# CLK.net
KiCad netlist of a schematic drawn in EAGLE
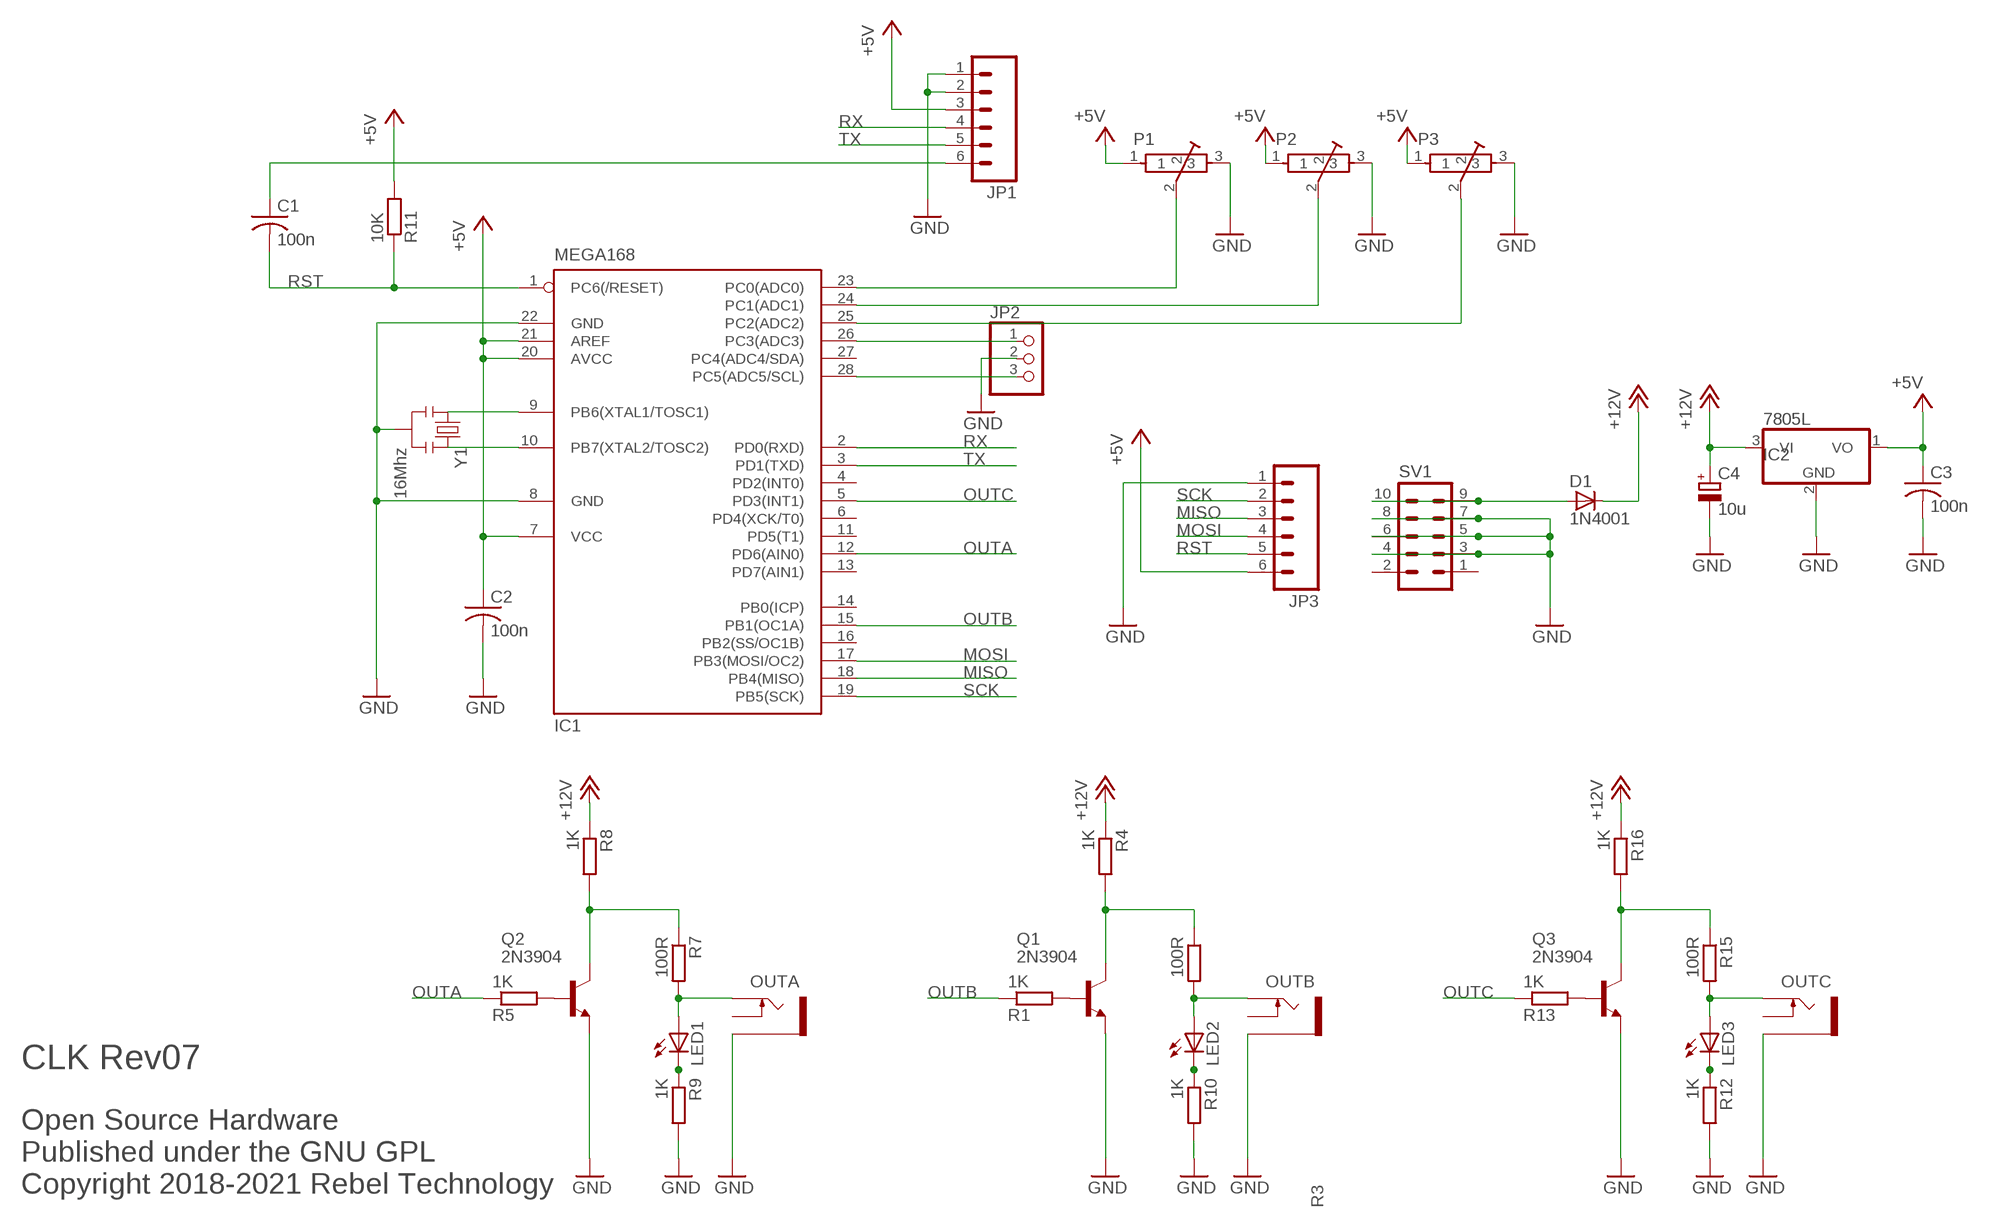
[diagram p0: schematic, sheet 1]

(export (version "E")
  (design (tool "Eeschema 10.0.6"))
  (components
    (comp (ref "C1")
      (value "100n")
      (footprint "eagle-import:C050-024X044")
      (libsource (lib "eagle-import") (part "C-US050-024X044"))
    )
    (comp (ref "C2")
      (value "100n")
      (footprint "eagle-import:C050-024X044")
      (libsource (lib "eagle-import") (part "C-US050-024X044"))
    )
    (comp (ref "C3")
      (value "100n")
      (footprint "eagle-import:C050-024X044")
      (libsource (lib "eagle-import") (part "C-US050-024X044"))
    )
    (comp (ref "C4")
      (value "10u")
      (footprint "eagle-import:E5-6")
      (libsource (lib "eagle-import") (part "CPOL-EUE5-6"))
    )
    (comp (ref "D1")
      (value "1N4001")
      (footprint "eagle-import:DIODE-1N4001")
      (libsource (lib "eagle-import") (part "DIODE1N4001"))
    )
    (comp (ref "IC1")
      (value "MEGA168")
      (footprint "eagle-import:DIL28-3")
      (libsource (lib "eagle-import") (part "MEGA8-P"))
    )
    (comp (ref "IC2")
      (value "7805L")
      (footprint "eagle-import:TO92")
      (libsource (lib "eagle-import") (part "78L05"))
    )
    (comp (ref "JP1")
      (value "M06SIP")
      (footprint "eagle-import:1X06")
      (libsource (lib "eagle-import") (part "M06SIP"))
    )
    (comp (ref "JP2")
      (value "PINHD-1X3")
      (footprint "eagle-import:1X03")
      (libsource (lib "eagle-import") (part "PINHD-1X3"))
    )
    (comp (ref "JP3")
      (value "M06SIP")
      (footprint "eagle-import:1X06")
      (libsource (lib "eagle-import") (part "M06SIP"))
    )
    (comp (ref "LED1")
      (value "LED3MM")
      (footprint "eagle-import:LED3MM")
      (libsource (lib "eagle-import") (part "LED3MM"))
    )
    (comp (ref "LED2")
      (value "LED3MM")
      (footprint "eagle-import:LED3MM")
      (libsource (lib "eagle-import") (part "LED3MM"))
    )
    (comp (ref "LED3")
      (value "LED3MM")
      (footprint "eagle-import:LED3MM")
      (libsource (lib "eagle-import") (part "LED3MM"))
    )
    (comp (ref "OUTA")
      (value "PJ302M")
      (footprint "eagle-import:PJ302M")
      (libsource (lib "eagle-import") (part "PJ302M"))
    )
    (comp (ref "OUTB")
      (value "PJ302M")
      (footprint "eagle-import:PJ302M")
      (libsource (lib "eagle-import") (part "PJ302M"))
    )
    (comp (ref "OUTC")
      (value "PJ302M")
      (footprint "eagle-import:PJ302M")
      (libsource (lib "eagle-import") (part "PJ302M"))
    )
    (comp (ref "P1")
      (value "POT-BOURNS-PTD901")
      (footprint "eagle-import:POT-BOURNS-PTD901")
      (libsource (lib "eagle-import") (part "POT-BOURNS-PTD901"))
    )
    (comp (ref "P2")
      (value "POT-BOURNS-PTD901")
      (footprint "eagle-import:POT-BOURNS-PTD901")
      (libsource (lib "eagle-import") (part "POT-BOURNS-PTD901"))
    )
    (comp (ref "P3")
      (value "POT-BOURNS-PTD901")
      (footprint "eagle-import:POT-BOURNS-PTD901")
      (libsource (lib "eagle-import") (part "POT-BOURNS-PTD901"))
    )
    (comp (ref "Q1")
      (value "2N3904")
      (footprint "eagle-import:TO92")
      (libsource (lib "eagle-import") (part "2N3904"))
    )
    (comp (ref "Q2")
      (value "2N3904")
      (footprint "eagle-import:TO92")
      (libsource (lib "eagle-import") (part "2N3904"))
    )
    (comp (ref "Q3")
      (value "2N3904")
      (footprint "eagle-import:TO92")
      (libsource (lib "eagle-import") (part "2N3904"))
    )
    (comp (ref "R1")
      (value "1K")
      (footprint "eagle-import:0204_7")
      (libsource (lib "eagle-import") (part "R-EU_0204/7"))
    )
    (comp (ref "R3")
      (value "100R")
      (footprint "eagle-import:0204_7")
      (libsource (lib "eagle-import") (part "R-EU_0204/7"))
    )
    (comp (ref "R4")
      (value "1K")
      (footprint "eagle-import:0204_7")
      (libsource (lib "eagle-import") (part "R-EU_0204/7"))
    )
    (comp (ref "R5")
      (value "1K")
      (footprint "eagle-import:0204_7")
      (libsource (lib "eagle-import") (part "R-EU_0204/7"))
    )
    (comp (ref "R7")
      (value "100R")
      (footprint "eagle-import:0204_7")
      (libsource (lib "eagle-import") (part "R-EU_0204/7"))
    )
    (comp (ref "R8")
      (value "1K")
      (footprint "eagle-import:0204_7")
      (libsource (lib "eagle-import") (part "R-EU_0204/7"))
    )
    (comp (ref "R9")
      (value "1K")
      (footprint "eagle-import:0204_7")
      (libsource (lib "eagle-import") (part "R-EU_0204/7"))
    )
    (comp (ref "R10")
      (value "1K")
      (footprint "eagle-import:0204_7")
      (libsource (lib "eagle-import") (part "R-EU_0204/7"))
    )
    (comp (ref "R11")
      (value "10K")
      (footprint "eagle-import:0204_7")
      (libsource (lib "eagle-import") (part "R-EU_0204/7"))
    )
    (comp (ref "R12")
      (value "1K")
      (footprint "eagle-import:0204_7")
      (libsource (lib "eagle-import") (part "R-EU_0204/7"))
    )
    (comp (ref "R13")
      (value "1K")
      (footprint "eagle-import:0204_7")
      (libsource (lib "eagle-import") (part "R-EU_0204/7"))
    )
    (comp (ref "R15")
      (value "100R")
      (footprint "eagle-import:0204_7")
      (libsource (lib "eagle-import") (part "R-EU_0204/7"))
    )
    (comp (ref "R16")
      (value "1K")
      (footprint "eagle-import:0204_7")
      (libsource (lib "eagle-import") (part "R-EU_0204/7"))
    )
    (comp (ref "SV1")
      (value "MA05-2")
      (footprint "eagle-import:MA05-2")
      (libsource (lib "eagle-import") (part "MA05-2"))
    )
    (comp (ref "Y1")
      (value "16Mhz")
      (footprint "eagle-import:RESONATOR-PTH")
      (libsource (lib "eagle-import") (part "RESONATORPTH"))
    )
  )
  (nets
    (net (code "1") (name "+5V") (class "Default")
      (node (ref "C2") (pin "1") (pinfunction "1_1") (pintype "passive"))
      (node (ref "C3") (pin "1") (pinfunction "1_1") (pintype "passive"))
      (node (ref "IC1") (pin "20") (pinfunction "AVCC_20") (pintype "power_in"))
      (node (ref "IC1") (pin "21") (pinfunction "AREF_21") (pintype "passive"))
      (node (ref "IC1") (pin "7") (pinfunction "VCC_7") (pintype "power_in"))
      (node (ref "IC2") (pin "1") (pinfunction "VO_1") (pintype "passive"))
      (node (ref "JP1") (pin "3") (pinfunction "3_3") (pintype "passive"))
      (node (ref "JP3") (pin "6") (pinfunction "6_6") (pintype "passive"))
      (node (ref "P1") (pin "1") (pinfunction "1_1") (pintype "bidirectional"))
      (node (ref "P2") (pin "1") (pinfunction "1_1") (pintype "bidirectional"))
      (node (ref "P3") (pin "1") (pinfunction "1_1") (pintype "bidirectional"))
      (node (ref "R11") (pin "2") (pinfunction "2_2") (pintype "passive"))
    )
    (net (code "2") (name "+12V") (class "Default")
      (node (ref "C4") (pin "+") (pinfunction "+_+") (pintype "passive"))
      (node (ref "D1") (pin "C") (pinfunction "C_C") (pintype "passive"))
      (node (ref "IC2") (pin "3") (pinfunction "VI_3") (pintype "input"))
      (node (ref "R16") (pin "1") (pinfunction "1_1") (pintype "passive"))
      (node (ref "R4") (pin "1") (pinfunction "1_1") (pintype "passive"))
      (node (ref "R8") (pin "1") (pinfunction "1_1") (pintype "passive"))
    )
    (net (code "3") (name "/MISO") (class "Default")
      (node (ref "IC1") (pin "18") (pinfunction "PB4(MISO)_18") (pintype "bidirectional"))
      (node (ref "JP3") (pin "3") (pinfunction "3_3") (pintype "passive"))
    )
    (net (code "4") (name "/MOSI") (class "Default")
      (node (ref "IC1") (pin "17") (pinfunction "PB3(MOSI/OC2)_17") (pintype "bidirectional"))
      (node (ref "JP3") (pin "4") (pinfunction "4_4") (pintype "passive"))
    )
    (net (code "5") (name "/OUTA") (class "Default")
      (node (ref "IC1") (pin "12") (pinfunction "PD6(AIN0)_12") (pintype "bidirectional"))
      (node (ref "R5") (pin "1") (pinfunction "1_1") (pintype "passive"))
    )
    (net (code "6") (name "/OUTB") (class "Default")
      (node (ref "IC1") (pin "15") (pinfunction "PB1(OC1A)_15") (pintype "bidirectional"))
      (node (ref "R1") (pin "1") (pinfunction "1_1") (pintype "passive"))
    )
    (net (code "7") (name "/OUTC") (class "Default")
      (node (ref "IC1") (pin "5") (pinfunction "PD3(INT1)_5") (pintype "bidirectional"))
      (node (ref "R13") (pin "1") (pinfunction "1_1") (pintype "passive"))
    )
    (net (code "8") (name "/RST") (class "Default")
      (node (ref "C1") (pin "2") (pinfunction "2_2") (pintype "passive"))
      (node (ref "IC1") (pin "1") (pinfunction "PC6(/RESET)_1") (pintype "bidirectional"))
      (node (ref "JP3") (pin "5") (pinfunction "5_5") (pintype "passive"))
      (node (ref "R11") (pin "1") (pinfunction "1_1") (pintype "passive"))
    )
    (net (code "9") (name "/RX") (class "Default")
      (node (ref "IC1") (pin "2") (pinfunction "PD0(RXD)_2") (pintype "bidirectional"))
      (node (ref "JP1") (pin "4") (pinfunction "4_4") (pintype "passive"))
    )
    (net (code "10") (name "/SCK") (class "Default")
      (node (ref "IC1") (pin "19") (pinfunction "PB5(SCK)_19") (pintype "bidirectional"))
      (node (ref "JP3") (pin "2") (pinfunction "2_2") (pintype "passive"))
    )
    (net (code "11") (name "/TX") (class "Default")
      (node (ref "IC1") (pin "3") (pinfunction "PD1(TXD)_3") (pintype "bidirectional"))
      (node (ref "JP1") (pin "5") (pinfunction "5_5") (pintype "passive"))
    )
    (net (code "12") (name "GND") (class "Default")
      (node (ref "C2") (pin "2") (pinfunction "2_2") (pintype "passive"))
      (node (ref "C3") (pin "2") (pinfunction "2_2") (pintype "passive"))
      (node (ref "C4") (pin "-") (pinfunction "-_-") (pintype "passive"))
      (node (ref "IC1") (pin "22") (pinfunction "GND_22") (pintype "power_in"))
      (node (ref "IC1") (pin "8") (pinfunction "GND_8") (pintype "power_in"))
      (node (ref "IC2") (pin "2") (pinfunction "GND_2") (pintype "passive"))
      (node (ref "JP1") (pin "1") (pinfunction "1_1") (pintype "passive"))
      (node (ref "JP1") (pin "2") (pinfunction "2_2") (pintype "passive"))
      (node (ref "JP2") (pin "2") (pinfunction "2_2") (pintype "passive"))
      (node (ref "JP3") (pin "1") (pinfunction "1_1") (pintype "passive"))
      (node (ref "OUTA") (pin "GND") (pinfunction "SLEEVE_GND") (pintype "passive"))
      (node (ref "OUTB") (pin "GND") (pinfunction "SLEEVE_GND") (pintype "passive"))
      (node (ref "OUTC") (pin "GND") (pinfunction "SLEEVE_GND") (pintype "passive"))
      (node (ref "P1") (pin "3") (pinfunction "3_3") (pintype "bidirectional"))
      (node (ref "P2") (pin "3") (pinfunction "3_3") (pintype "bidirectional"))
      (node (ref "P3") (pin "3") (pinfunction "3_3") (pintype "bidirectional"))
      (node (ref "Q1") (pin "3") (pinfunction "E_3") (pintype "passive"))
      (node (ref "Q2") (pin "3") (pinfunction "E_3") (pintype "passive"))
      (node (ref "Q3") (pin "3") (pinfunction "E_3") (pintype "passive"))
      (node (ref "R10") (pin "2") (pinfunction "2_2") (pintype "passive"))
      (node (ref "R12") (pin "2") (pinfunction "2_2") (pintype "passive"))
      (node (ref "R9") (pin "2") (pinfunction "2_2") (pintype "passive"))
      (node (ref "SV1") (pin "3") (pinfunction "3_3") (pintype "passive"))
      (node (ref "SV1") (pin "4") (pinfunction "4_4") (pintype "passive"))
      (node (ref "SV1") (pin "5") (pinfunction "5_5") (pintype "passive"))
      (node (ref "SV1") (pin "6") (pinfunction "6_6") (pintype "passive"))
      (node (ref "SV1") (pin "7") (pinfunction "7_7") (pintype "passive"))
      (node (ref "SV1") (pin "8") (pinfunction "8_8") (pintype "passive"))
      (node (ref "Y1") (pin "2") (pinfunction "2_2") (pintype "passive"))
    )
    (net (code "13") (name "Net-(C1-Pad1)") (class "Default")
      (node (ref "C1") (pin "1") (pinfunction "1_1") (pintype "passive"))
      (node (ref "JP1") (pin "6") (pinfunction "6_6") (pintype "passive"))
    )
    (net (code "14") (name "Net-(D1-PadA)") (class "Default")
      (node (ref "D1") (pin "A") (pinfunction "A_A") (pintype "passive"))
      (node (ref "SV1") (pin "10") (pinfunction "10_10") (pintype "passive"))
      (node (ref "SV1") (pin "9") (pinfunction "9_9") (pintype "passive"))
    )
    (net (code "15") (name "Net-(IC1-PB6(XTAL1{slash}TOSC1))") (class "Default")
      (node (ref "IC1") (pin "9") (pinfunction "PB6(XTAL1/TOSC1)_9") (pintype "bidirectional"))
      (node (ref "Y1") (pin "1") (pinfunction "1_1") (pintype "passive"))
    )
    (net (code "16") (name "Net-(IC1-PB7(XTAL2{slash}TOSC2))") (class "Default")
      (node (ref "IC1") (pin "10") (pinfunction "PB7(XTAL2/TOSC2)_10") (pintype "bidirectional"))
      (node (ref "Y1") (pin "3") (pinfunction "3_3") (pintype "passive"))
    )
    (net (code "17") (name "Net-(IC1-PC0(ADC0))") (class "Default")
      (node (ref "IC1") (pin "23") (pinfunction "PC0(ADC0)_23") (pintype "bidirectional"))
      (node (ref "P1") (pin "2") (pinfunction "2_2") (pintype "bidirectional"))
    )
    (net (code "18") (name "Net-(IC1-PC1(ADC1))") (class "Default")
      (node (ref "IC1") (pin "24") (pinfunction "PC1(ADC1)_24") (pintype "bidirectional"))
      (node (ref "P2") (pin "2") (pinfunction "2_2") (pintype "bidirectional"))
    )
    (net (code "19") (name "Net-(IC1-PC2(ADC2))") (class "Default")
      (node (ref "IC1") (pin "25") (pinfunction "PC2(ADC2)_25") (pintype "bidirectional"))
      (node (ref "P3") (pin "2") (pinfunction "2_2") (pintype "bidirectional"))
    )
    (net (code "20") (name "Net-(IC1-PC3(ADC3))") (class "Default")
      (node (ref "IC1") (pin "26") (pinfunction "PC3(ADC3)_26") (pintype "bidirectional"))
      (node (ref "JP2") (pin "1") (pinfunction "1_1") (pintype "passive"))
    )
    (net (code "21") (name "Net-(IC1-PC5(ADC5{slash}SCL))") (class "Default")
      (node (ref "IC1") (pin "28") (pinfunction "PC5(ADC5/SCL)_28") (pintype "bidirectional"))
      (node (ref "JP2") (pin "3") (pinfunction "3_3") (pintype "passive"))
    )
    (net (code "22") (name "Net-(LED1-C)") (class "Default")
      (node (ref "LED1") (pin "K") (pinfunction "C_K") (pintype "passive"))
      (node (ref "R9") (pin "1") (pinfunction "1_1") (pintype "passive"))
    )
    (net (code "23") (name "Net-(LED1-PadA)") (class "Default")
      (node (ref "LED1") (pin "A") (pinfunction "A_A") (pintype "passive"))
      (node (ref "OUTA") (pin "TIP") (pinfunction "TIP_TIP") (pintype "passive"))
      (node (ref "R7") (pin "2") (pinfunction "2_2") (pintype "passive"))
    )
    (net (code "24") (name "Net-(LED2-C)") (class "Default")
      (node (ref "LED2") (pin "K") (pinfunction "C_K") (pintype "passive"))
      (node (ref "R10") (pin "1") (pinfunction "1_1") (pintype "passive"))
    )
    (net (code "25") (name "Net-(LED2-PadA)") (class "Default")
      (node (ref "LED2") (pin "A") (pinfunction "A_A") (pintype "passive"))
      (node (ref "OUTB") (pin "TIP") (pinfunction "TIP_TIP") (pintype "passive"))
      (node (ref "R3") (pin "2") (pinfunction "2_2") (pintype "passive"))
    )
    (net (code "26") (name "Net-(LED3-C)") (class "Default")
      (node (ref "LED3") (pin "K") (pinfunction "C_K") (pintype "passive"))
      (node (ref "R12") (pin "1") (pinfunction "1_1") (pintype "passive"))
    )
    (net (code "27") (name "Net-(LED3-PadA)") (class "Default")
      (node (ref "LED3") (pin "A") (pinfunction "A_A") (pintype "passive"))
      (node (ref "OUTC") (pin "TIP") (pinfunction "TIP_TIP") (pintype "passive"))
      (node (ref "R15") (pin "2") (pinfunction "2_2") (pintype "passive"))
    )
    (net (code "28") (name "Net-(Q1-B)") (class "Default")
      (node (ref "Q1") (pin "2") (pinfunction "B_2") (pintype "passive"))
      (node (ref "R1") (pin "2") (pinfunction "2_2") (pintype "passive"))
    )
    (net (code "29") (name "Net-(Q1-C)") (class "Default")
      (node (ref "Q1") (pin "1") (pinfunction "C_1") (pintype "passive"))
      (node (ref "R3") (pin "1") (pinfunction "1_1") (pintype "passive"))
      (node (ref "R4") (pin "2") (pinfunction "2_2") (pintype "passive"))
    )
    (net (code "30") (name "Net-(Q2-B)") (class "Default")
      (node (ref "Q2") (pin "2") (pinfunction "B_2") (pintype "passive"))
      (node (ref "R5") (pin "2") (pinfunction "2_2") (pintype "passive"))
    )
    (net (code "31") (name "Net-(Q2-C)") (class "Default")
      (node (ref "Q2") (pin "1") (pinfunction "C_1") (pintype "passive"))
      (node (ref "R7") (pin "1") (pinfunction "1_1") (pintype "passive"))
      (node (ref "R8") (pin "2") (pinfunction "2_2") (pintype "passive"))
    )
    (net (code "32") (name "Net-(Q3-B)") (class "Default")
      (node (ref "Q3") (pin "2") (pinfunction "B_2") (pintype "passive"))
      (node (ref "R13") (pin "2") (pinfunction "2_2") (pintype "passive"))
    )
    (net (code "33") (name "Net-(Q3-C)") (class "Default")
      (node (ref "Q3") (pin "1") (pinfunction "C_1") (pintype "passive"))
      (node (ref "R15") (pin "1") (pinfunction "1_1") (pintype "passive"))
      (node (ref "R16") (pin "2") (pinfunction "2_2") (pintype "passive"))
    )
    (net (code "34") (name "unconnected-(IC1-PB0(ICP)-Pad14)") (class "Default")
      (node (ref "IC1") (pin "14") (pinfunction "PB0(ICP)_14") (pintype "bidirectional"))
    )
    (net (code "35") (name "unconnected-(IC1-PB2(SS{slash}OC1B)-Pad16)") (class "Default")
      (node (ref "IC1") (pin "16") (pinfunction "PB2(SS/OC1B)_16") (pintype "bidirectional"))
    )
    (net (code "36") (name "unconnected-(IC1-PC4(ADC4{slash}SDA)-Pad27)") (class "Default")
      (node (ref "IC1") (pin "27") (pinfunction "PC4(ADC4/SDA)_27") (pintype "bidirectional"))
    )
    (net (code "37") (name "unconnected-(IC1-PD2(INT0)-Pad4)") (class "Default")
      (node (ref "IC1") (pin "4") (pinfunction "PD2(INT0)_4") (pintype "bidirectional"))
    )
    (net (code "38") (name "unconnected-(IC1-PD4(XCK{slash}T0)-Pad6)") (class "Default")
      (node (ref "IC1") (pin "6") (pinfunction "PD4(XCK/T0)_6") (pintype "bidirectional"))
    )
    (net (code "39") (name "unconnected-(IC1-PD5(T1)-Pad11)") (class "Default")
      (node (ref "IC1") (pin "11") (pinfunction "PD5(T1)_11") (pintype "bidirectional"))
    )
    (net (code "40") (name "unconnected-(IC1-PD7(AIN1)-Pad13)") (class "Default")
      (node (ref "IC1") (pin "13") (pinfunction "PD7(AIN1)_13") (pintype "bidirectional"))
    )
    (net (code "41") (name "unconnected-(OUTA-SWITCH-PadSW)") (class "Default")
      (node (ref "OUTA") (pin "SW") (pinfunction "SWITCH_SW") (pintype "passive"))
    )
    (net (code "42") (name "unconnected-(OUTB-SWITCH-PadSW)") (class "Default")
      (node (ref "OUTB") (pin "SW") (pinfunction "SWITCH_SW") (pintype "passive"))
    )
    (net (code "43") (name "unconnected-(OUTC-SWITCH-PadSW)") (class "Default")
      (node (ref "OUTC") (pin "SW") (pinfunction "SWITCH_SW") (pintype "passive"))
    )
    (net (code "44") (name "unconnected-(SV1-Pad1)") (class "Default")
      (node (ref "SV1") (pin "1") (pinfunction "1_1") (pintype "passive"))
    )
    (net (code "45") (name "unconnected-(SV1-Pad2)") (class "Default")
      (node (ref "SV1") (pin "2") (pinfunction "2_2") (pintype "passive"))
    )
  )
)
